# HexJacks.net
KiCad netlist of a schematic drawn in EAGLE
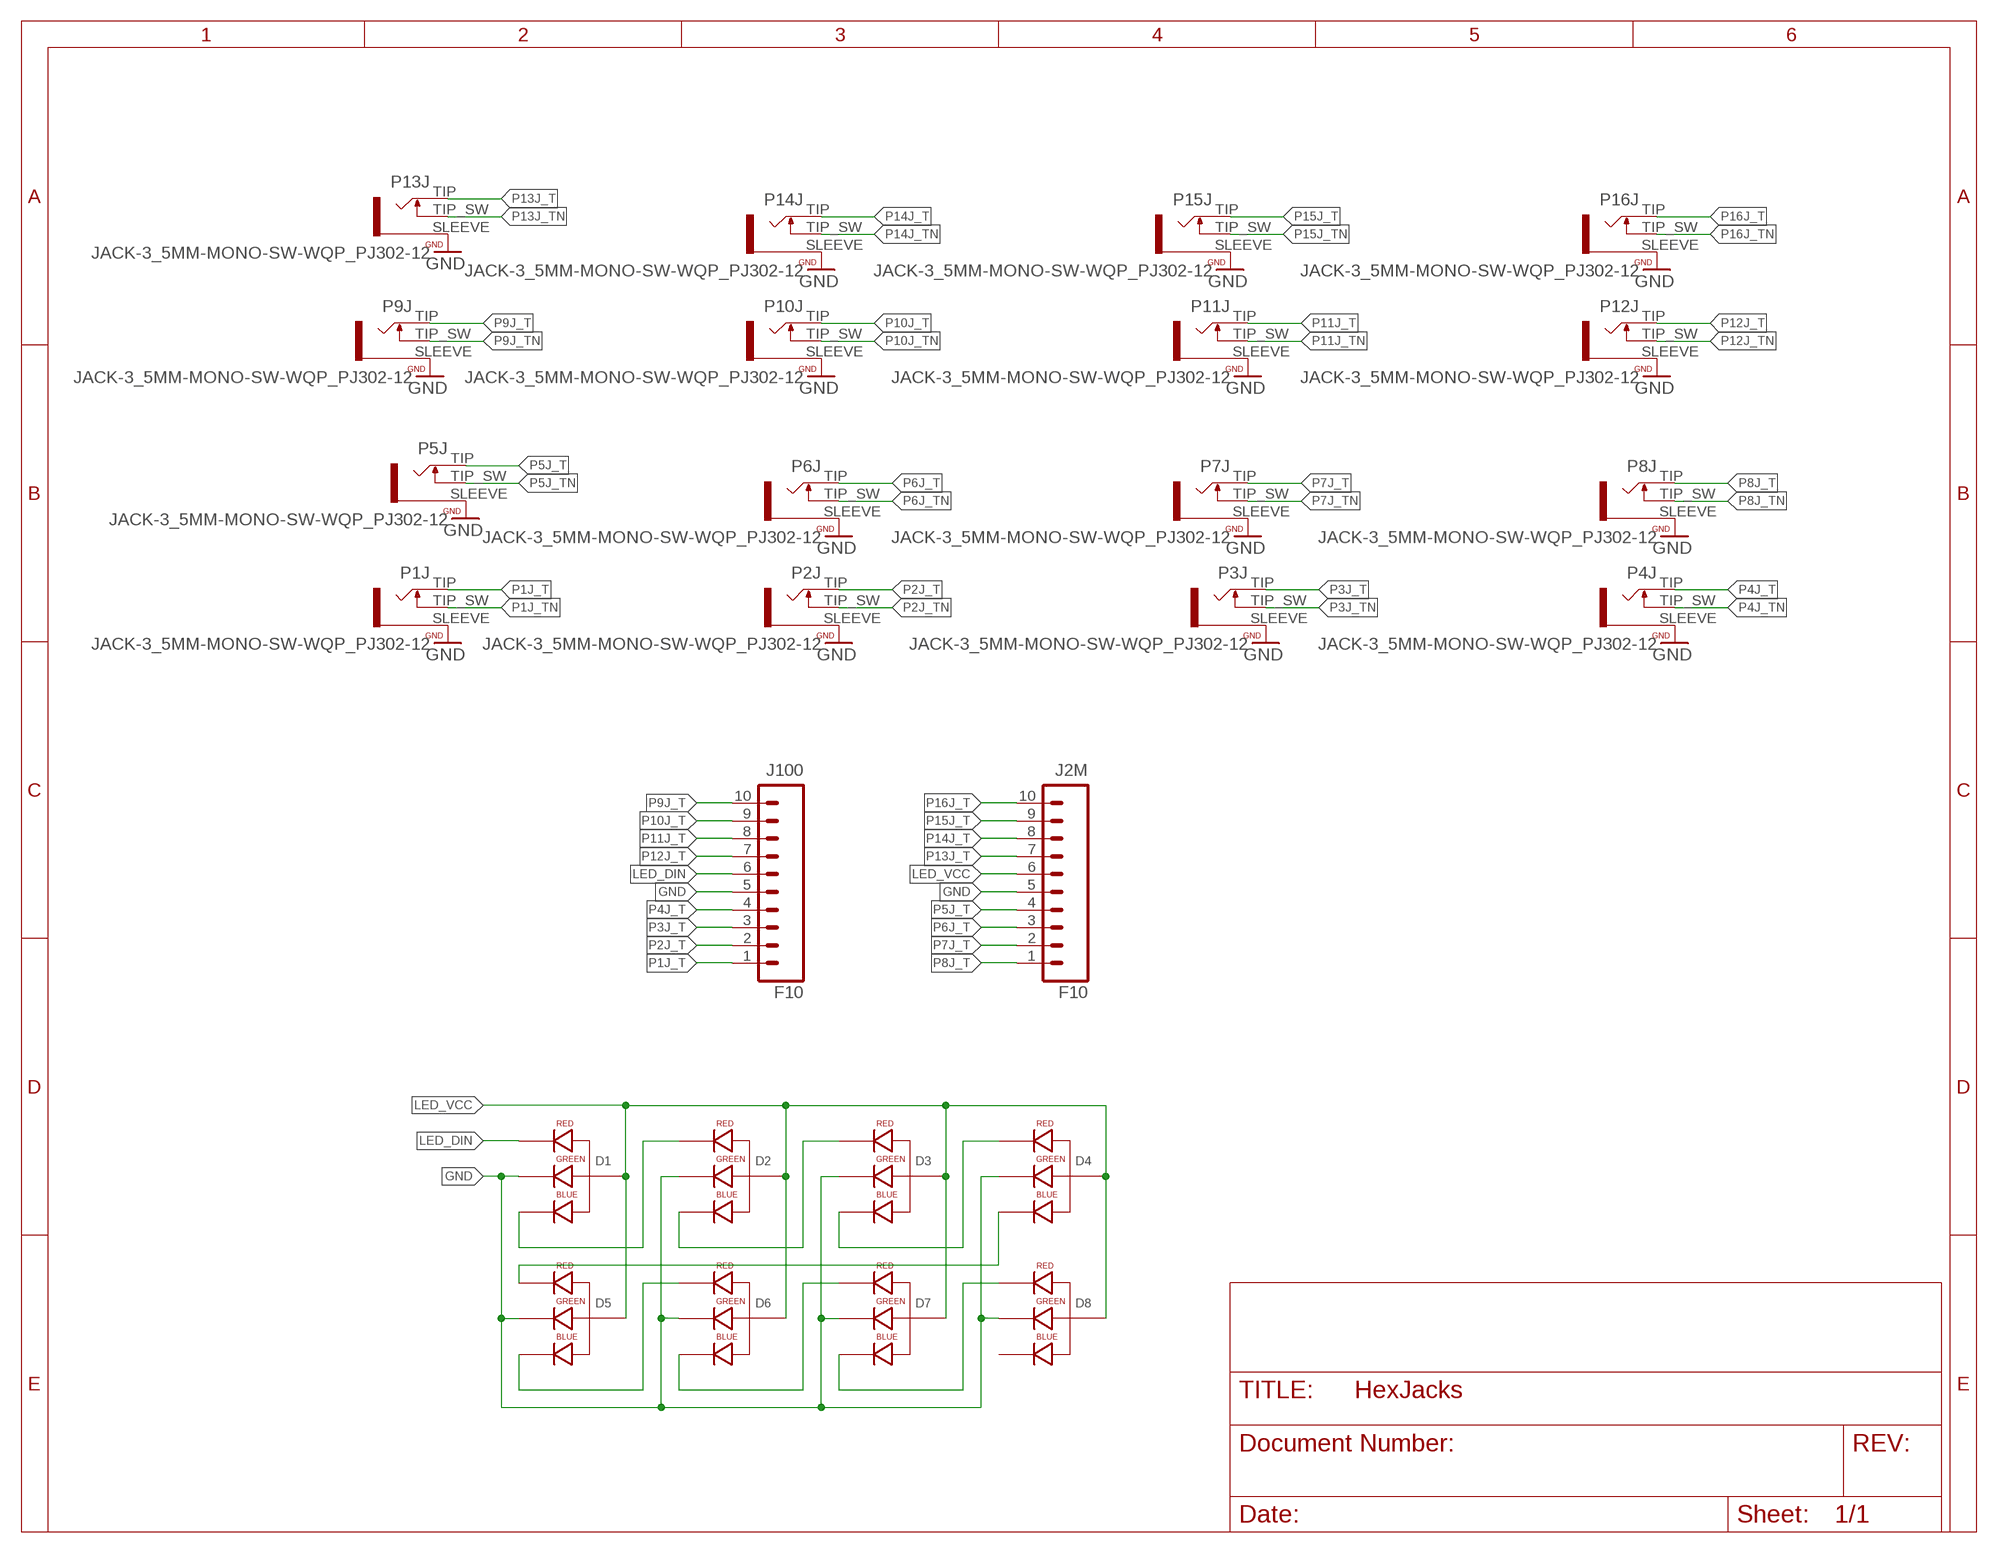
[diagram p0: schematic, sheet 1]

(export (version "E")
  (design (tool "Eeschema 10.0.6"))
  (components
    (comp (ref "D1")
      (value "LED-RGB-CA-THRUCLEAR")
      (footprint "eagle-import:LED-RGB-THRU")
      (libsource (lib "eagle-import") (part "LED-RGB-CA-THRUCLEAR"))
    )
    (comp (ref "D2")
      (value "LED-RGB-CA-THRUCLEAR")
      (footprint "eagle-import:LED-RGB-THRU")
      (libsource (lib "eagle-import") (part "LED-RGB-CA-THRUCLEAR"))
    )
    (comp (ref "D3")
      (value "LED-RGB-CA-THRUCLEAR")
      (footprint "eagle-import:LED-RGB-THRU")
      (libsource (lib "eagle-import") (part "LED-RGB-CA-THRUCLEAR"))
    )
    (comp (ref "D4")
      (value "LED-RGB-CA-THRUCLEAR")
      (footprint "eagle-import:LED-RGB-THRU")
      (libsource (lib "eagle-import") (part "LED-RGB-CA-THRUCLEAR"))
    )
    (comp (ref "D5")
      (value "LED-RGB-CA-THRUCLEAR")
      (footprint "eagle-import:LED-RGB-THRU")
      (libsource (lib "eagle-import") (part "LED-RGB-CA-THRUCLEAR"))
    )
    (comp (ref "D6")
      (value "LED-RGB-CA-THRUCLEAR")
      (footprint "eagle-import:LED-RGB-THRU")
      (libsource (lib "eagle-import") (part "LED-RGB-CA-THRUCLEAR"))
    )
    (comp (ref "D7")
      (value "LED-RGB-CA-THRUCLEAR")
      (footprint "eagle-import:LED-RGB-THRU")
      (libsource (lib "eagle-import") (part "LED-RGB-CA-THRUCLEAR"))
    )
    (comp (ref "D8")
      (value "LED-RGB-CA-THRUCLEAR")
      (footprint "eagle-import:LED-RGB-THRU")
      (libsource (lib "eagle-import") (part "LED-RGB-CA-THRUCLEAR"))
    )
    (comp (ref "J2M")
      (value "F10")
      (footprint "eagle-import:1X10_OCTO")
      (libsource (lib "eagle-import") (part "M10SILK_FEMALE_PTH"))
    )
    (comp (ref "J100")
      (value "F10")
      (footprint "eagle-import:1X10_OCTO")
      (libsource (lib "eagle-import") (part "M10SILK_FEMALE_PTH"))
    )
    (comp (ref "P1J")
      (value "JACK-3_5MM-MONO-SW-WQP_PJ302-12")
      (footprint "eagle-import:WQP_PJ301M-12")
      (libsource (lib "eagle-import") (part "JACK-3_5MM-MONO-SW-WQP_PJ302-12"))
    )
    (comp (ref "P2J")
      (value "JACK-3_5MM-MONO-SW-WQP_PJ302-12")
      (footprint "eagle-import:WQP_PJ301M-12")
      (libsource (lib "eagle-import") (part "JACK-3_5MM-MONO-SW-WQP_PJ302-12"))
    )
    (comp (ref "P3J")
      (value "JACK-3_5MM-MONO-SW-WQP_PJ302-12")
      (footprint "eagle-import:WQP_PJ301M-12")
      (libsource (lib "eagle-import") (part "JACK-3_5MM-MONO-SW-WQP_PJ302-12"))
    )
    (comp (ref "P4J")
      (value "JACK-3_5MM-MONO-SW-WQP_PJ302-12")
      (footprint "eagle-import:WQP_PJ301M-12")
      (libsource (lib "eagle-import") (part "JACK-3_5MM-MONO-SW-WQP_PJ302-12"))
    )
    (comp (ref "P5J")
      (value "JACK-3_5MM-MONO-SW-WQP_PJ302-12")
      (footprint "eagle-import:WQP_PJ301M-12")
      (libsource (lib "eagle-import") (part "JACK-3_5MM-MONO-SW-WQP_PJ302-12"))
    )
    (comp (ref "P6J")
      (value "JACK-3_5MM-MONO-SW-WQP_PJ302-12")
      (footprint "eagle-import:WQP_PJ301M-12")
      (libsource (lib "eagle-import") (part "JACK-3_5MM-MONO-SW-WQP_PJ302-12"))
    )
    (comp (ref "P7J")
      (value "JACK-3_5MM-MONO-SW-WQP_PJ302-12")
      (footprint "eagle-import:WQP_PJ301M-12")
      (libsource (lib "eagle-import") (part "JACK-3_5MM-MONO-SW-WQP_PJ302-12"))
    )
    (comp (ref "P8J")
      (value "JACK-3_5MM-MONO-SW-WQP_PJ302-12")
      (footprint "eagle-import:WQP_PJ301M-12")
      (libsource (lib "eagle-import") (part "JACK-3_5MM-MONO-SW-WQP_PJ302-12"))
    )
    (comp (ref "P9J")
      (value "JACK-3_5MM-MONO-SW-WQP_PJ302-12")
      (footprint "eagle-import:WQP_PJ301M-12")
      (libsource (lib "eagle-import") (part "JACK-3_5MM-MONO-SW-WQP_PJ302-12"))
    )
    (comp (ref "P10J")
      (value "JACK-3_5MM-MONO-SW-WQP_PJ302-12")
      (footprint "eagle-import:WQP_PJ301M-12")
      (libsource (lib "eagle-import") (part "JACK-3_5MM-MONO-SW-WQP_PJ302-12"))
    )
    (comp (ref "P11J")
      (value "JACK-3_5MM-MONO-SW-WQP_PJ302-12")
      (footprint "eagle-import:WQP_PJ301M-12")
      (libsource (lib "eagle-import") (part "JACK-3_5MM-MONO-SW-WQP_PJ302-12"))
    )
    (comp (ref "P12J")
      (value "JACK-3_5MM-MONO-SW-WQP_PJ302-12")
      (footprint "eagle-import:WQP_PJ301M-12")
      (libsource (lib "eagle-import") (part "JACK-3_5MM-MONO-SW-WQP_PJ302-12"))
    )
    (comp (ref "P13J")
      (value "JACK-3_5MM-MONO-SW-WQP_PJ302-12")
      (footprint "eagle-import:WQP_PJ301M-12")
      (libsource (lib "eagle-import") (part "JACK-3_5MM-MONO-SW-WQP_PJ302-12"))
    )
    (comp (ref "P14J")
      (value "JACK-3_5MM-MONO-SW-WQP_PJ302-12")
      (footprint "eagle-import:WQP_PJ301M-12")
      (libsource (lib "eagle-import") (part "JACK-3_5MM-MONO-SW-WQP_PJ302-12"))
    )
    (comp (ref "P15J")
      (value "JACK-3_5MM-MONO-SW-WQP_PJ302-12")
      (footprint "eagle-import:WQP_PJ301M-12")
      (libsource (lib "eagle-import") (part "JACK-3_5MM-MONO-SW-WQP_PJ302-12"))
    )
    (comp (ref "P16J")
      (value "JACK-3_5MM-MONO-SW-WQP_PJ302-12")
      (footprint "eagle-import:WQP_PJ301M-12")
      (libsource (lib "eagle-import") (part "JACK-3_5MM-MONO-SW-WQP_PJ302-12"))
    )
  )
  (nets
    (net (code "1") (name "GND") (class "Default")
      (node (ref "D1") (pin "3") (pinfunction "GREEN_CATHODE_3") (pintype "bidirectional"))
      (node (ref "D2") (pin "3") (pinfunction "GREEN_CATHODE_3") (pintype "bidirectional"))
      (node (ref "D3") (pin "3") (pinfunction "GREEN_CATHODE_3") (pintype "bidirectional"))
      (node (ref "D4") (pin "3") (pinfunction "GREEN_CATHODE_3") (pintype "bidirectional"))
      (node (ref "D5") (pin "3") (pinfunction "GREEN_CATHODE_3") (pintype "bidirectional"))
      (node (ref "D6") (pin "3") (pinfunction "GREEN_CATHODE_3") (pintype "bidirectional"))
      (node (ref "D7") (pin "3") (pinfunction "GREEN_CATHODE_3") (pintype "bidirectional"))
      (node (ref "D8") (pin "3") (pinfunction "GREEN_CATHODE_3") (pintype "bidirectional"))
      (node (ref "J100") (pin "5") (pinfunction "5_5") (pintype "passive"))
      (node (ref "J2M") (pin "5") (pinfunction "5_5") (pintype "passive"))
      (node (ref "P10J") (pin "SLEEVE") (pinfunction "SLEEVE_SLEEVE") (pintype "passive"))
      (node (ref "P11J") (pin "SLEEVE") (pinfunction "SLEEVE_SLEEVE") (pintype "passive"))
      (node (ref "P12J") (pin "SLEEVE") (pinfunction "SLEEVE_SLEEVE") (pintype "passive"))
      (node (ref "P13J") (pin "SLEEVE") (pinfunction "SLEEVE_SLEEVE") (pintype "passive"))
      (node (ref "P14J") (pin "SLEEVE") (pinfunction "SLEEVE_SLEEVE") (pintype "passive"))
      (node (ref "P15J") (pin "SLEEVE") (pinfunction "SLEEVE_SLEEVE") (pintype "passive"))
      (node (ref "P16J") (pin "SLEEVE") (pinfunction "SLEEVE_SLEEVE") (pintype "passive"))
      (node (ref "P1J") (pin "SLEEVE") (pinfunction "SLEEVE_SLEEVE") (pintype "passive"))
      (node (ref "P2J") (pin "SLEEVE") (pinfunction "SLEEVE_SLEEVE") (pintype "passive"))
      (node (ref "P3J") (pin "SLEEVE") (pinfunction "SLEEVE_SLEEVE") (pintype "passive"))
      (node (ref "P4J") (pin "SLEEVE") (pinfunction "SLEEVE_SLEEVE") (pintype "passive"))
      (node (ref "P5J") (pin "SLEEVE") (pinfunction "SLEEVE_SLEEVE") (pintype "passive"))
      (node (ref "P6J") (pin "SLEEVE") (pinfunction "SLEEVE_SLEEVE") (pintype "passive"))
      (node (ref "P7J") (pin "SLEEVE") (pinfunction "SLEEVE_SLEEVE") (pintype "passive"))
      (node (ref "P8J") (pin "SLEEVE") (pinfunction "SLEEVE_SLEEVE") (pintype "passive"))
      (node (ref "P9J") (pin "SLEEVE") (pinfunction "SLEEVE_SLEEVE") (pintype "passive"))
    )
    (net (code "2") (name "LED_DIN") (class "Default")
      (node (ref "D1") (pin "1") (pinfunction "RED_CATHODE_1") (pintype "bidirectional"))
      (node (ref "J100") (pin "6") (pinfunction "6_6") (pintype "passive"))
    )
    (net (code "3") (name "LED_VCC") (class "Default")
      (node (ref "D1") (pin "2") (pinfunction "ANODE_2") (pintype "bidirectional"))
      (node (ref "D2") (pin "2") (pinfunction "ANODE_2") (pintype "bidirectional"))
      (node (ref "D3") (pin "2") (pinfunction "ANODE_2") (pintype "bidirectional"))
      (node (ref "D4") (pin "2") (pinfunction "ANODE_2") (pintype "bidirectional"))
      (node (ref "D5") (pin "2") (pinfunction "ANODE_2") (pintype "bidirectional"))
      (node (ref "D6") (pin "2") (pinfunction "ANODE_2") (pintype "bidirectional"))
      (node (ref "D7") (pin "2") (pinfunction "ANODE_2") (pintype "bidirectional"))
      (node (ref "D8") (pin "2") (pinfunction "ANODE_2") (pintype "bidirectional"))
      (node (ref "J2M") (pin "6") (pinfunction "6_6") (pintype "passive"))
    )
    (net (code "4") (name "Net-(D1-BLUE_CATHODE)") (class "Default")
      (node (ref "D1") (pin "4") (pinfunction "BLUE_CATHODE_4") (pintype "bidirectional"))
      (node (ref "D2") (pin "1") (pinfunction "RED_CATHODE_1") (pintype "bidirectional"))
    )
    (net (code "5") (name "Net-(D2-BLUE_CATHODE)") (class "Default")
      (node (ref "D2") (pin "4") (pinfunction "BLUE_CATHODE_4") (pintype "bidirectional"))
      (node (ref "D3") (pin "1") (pinfunction "RED_CATHODE_1") (pintype "bidirectional"))
    )
    (net (code "6") (name "Net-(D3-BLUE_CATHODE)") (class "Default")
      (node (ref "D3") (pin "4") (pinfunction "BLUE_CATHODE_4") (pintype "bidirectional"))
      (node (ref "D4") (pin "1") (pinfunction "RED_CATHODE_1") (pintype "bidirectional"))
    )
    (net (code "7") (name "Net-(D4-BLUE_CATHODE)") (class "Default")
      (node (ref "D4") (pin "4") (pinfunction "BLUE_CATHODE_4") (pintype "bidirectional"))
      (node (ref "D5") (pin "1") (pinfunction "RED_CATHODE_1") (pintype "bidirectional"))
    )
    (net (code "8") (name "Net-(D5-BLUE_CATHODE)") (class "Default")
      (node (ref "D5") (pin "4") (pinfunction "BLUE_CATHODE_4") (pintype "bidirectional"))
      (node (ref "D6") (pin "1") (pinfunction "RED_CATHODE_1") (pintype "bidirectional"))
    )
    (net (code "9") (name "Net-(D6-BLUE_CATHODE)") (class "Default")
      (node (ref "D6") (pin "4") (pinfunction "BLUE_CATHODE_4") (pintype "bidirectional"))
      (node (ref "D7") (pin "1") (pinfunction "RED_CATHODE_1") (pintype "bidirectional"))
    )
    (net (code "10") (name "Net-(D7-BLUE_CATHODE)") (class "Default")
      (node (ref "D7") (pin "4") (pinfunction "BLUE_CATHODE_4") (pintype "bidirectional"))
      (node (ref "D8") (pin "1") (pinfunction "RED_CATHODE_1") (pintype "bidirectional"))
    )
    (net (code "11") (name "P1J_T") (class "Default")
      (node (ref "J100") (pin "1") (pinfunction "1_1") (pintype "passive"))
      (node (ref "P1J") (pin "TIP") (pinfunction "TIP_TIP") (pintype "passive"))
    )
    (net (code "12") (name "P1J_TN") (class "Default")
      (node (ref "P1J") (pin "TIP_SW") (pinfunction "TIP_SW_TIP_SW") (pintype "passive"))
    )
    (net (code "13") (name "P2J_T") (class "Default")
      (node (ref "J100") (pin "2") (pinfunction "2_2") (pintype "passive"))
      (node (ref "P2J") (pin "TIP") (pinfunction "TIP_TIP") (pintype "passive"))
    )
    (net (code "14") (name "P2J_TN") (class "Default")
      (node (ref "P2J") (pin "TIP_SW") (pinfunction "TIP_SW_TIP_SW") (pintype "passive"))
    )
    (net (code "15") (name "P3J_T") (class "Default")
      (node (ref "J100") (pin "3") (pinfunction "3_3") (pintype "passive"))
      (node (ref "P3J") (pin "TIP") (pinfunction "TIP_TIP") (pintype "passive"))
    )
    (net (code "16") (name "P3J_TN") (class "Default")
      (node (ref "P3J") (pin "TIP_SW") (pinfunction "TIP_SW_TIP_SW") (pintype "passive"))
    )
    (net (code "17") (name "P4J_T") (class "Default")
      (node (ref "J100") (pin "4") (pinfunction "4_4") (pintype "passive"))
      (node (ref "P4J") (pin "TIP") (pinfunction "TIP_TIP") (pintype "passive"))
    )
    (net (code "18") (name "P4J_TN") (class "Default")
      (node (ref "P4J") (pin "TIP_SW") (pinfunction "TIP_SW_TIP_SW") (pintype "passive"))
    )
    (net (code "19") (name "P5J_T") (class "Default")
      (node (ref "J2M") (pin "4") (pinfunction "4_4") (pintype "passive"))
      (node (ref "P5J") (pin "TIP") (pinfunction "TIP_TIP") (pintype "passive"))
    )
    (net (code "20") (name "P5J_TN") (class "Default")
      (node (ref "P5J") (pin "TIP_SW") (pinfunction "TIP_SW_TIP_SW") (pintype "passive"))
    )
    (net (code "21") (name "P6J_T") (class "Default")
      (node (ref "J2M") (pin "3") (pinfunction "3_3") (pintype "passive"))
      (node (ref "P6J") (pin "TIP") (pinfunction "TIP_TIP") (pintype "passive"))
    )
    (net (code "22") (name "P6J_TN") (class "Default")
      (node (ref "P6J") (pin "TIP_SW") (pinfunction "TIP_SW_TIP_SW") (pintype "passive"))
    )
    (net (code "23") (name "P7J_T") (class "Default")
      (node (ref "J2M") (pin "2") (pinfunction "2_2") (pintype "passive"))
      (node (ref "P7J") (pin "TIP") (pinfunction "TIP_TIP") (pintype "passive"))
    )
    (net (code "24") (name "P7J_TN") (class "Default")
      (node (ref "P7J") (pin "TIP_SW") (pinfunction "TIP_SW_TIP_SW") (pintype "passive"))
    )
    (net (code "25") (name "P8J_T") (class "Default")
      (node (ref "J2M") (pin "1") (pinfunction "1_1") (pintype "passive"))
      (node (ref "P8J") (pin "TIP") (pinfunction "TIP_TIP") (pintype "passive"))
    )
    (net (code "26") (name "P8J_TN") (class "Default")
      (node (ref "P8J") (pin "TIP_SW") (pinfunction "TIP_SW_TIP_SW") (pintype "passive"))
    )
    (net (code "27") (name "P9J_T") (class "Default")
      (node (ref "J100") (pin "10") (pinfunction "10_10") (pintype "passive"))
      (node (ref "P9J") (pin "TIP") (pinfunction "TIP_TIP") (pintype "passive"))
    )
    (net (code "28") (name "P9J_TN") (class "Default")
      (node (ref "P9J") (pin "TIP_SW") (pinfunction "TIP_SW_TIP_SW") (pintype "passive"))
    )
    (net (code "29") (name "P10J_T") (class "Default")
      (node (ref "J100") (pin "9") (pinfunction "9_9") (pintype "passive"))
      (node (ref "P10J") (pin "TIP") (pinfunction "TIP_TIP") (pintype "passive"))
    )
    (net (code "30") (name "P10J_TN") (class "Default")
      (node (ref "P10J") (pin "TIP_SW") (pinfunction "TIP_SW_TIP_SW") (pintype "passive"))
    )
    (net (code "31") (name "P11J_T") (class "Default")
      (node (ref "J100") (pin "8") (pinfunction "8_8") (pintype "passive"))
      (node (ref "P11J") (pin "TIP") (pinfunction "TIP_TIP") (pintype "passive"))
    )
    (net (code "32") (name "P11J_TN") (class "Default")
      (node (ref "P11J") (pin "TIP_SW") (pinfunction "TIP_SW_TIP_SW") (pintype "passive"))
    )
    (net (code "33") (name "P12J_T") (class "Default")
      (node (ref "J100") (pin "7") (pinfunction "7_7") (pintype "passive"))
      (node (ref "P12J") (pin "TIP") (pinfunction "TIP_TIP") (pintype "passive"))
    )
    (net (code "34") (name "P12J_TN") (class "Default")
      (node (ref "P12J") (pin "TIP_SW") (pinfunction "TIP_SW_TIP_SW") (pintype "passive"))
    )
    (net (code "35") (name "P13J_T") (class "Default")
      (node (ref "J2M") (pin "7") (pinfunction "7_7") (pintype "passive"))
      (node (ref "P13J") (pin "TIP") (pinfunction "TIP_TIP") (pintype "passive"))
    )
    (net (code "36") (name "P13J_TN") (class "Default")
      (node (ref "P13J") (pin "TIP_SW") (pinfunction "TIP_SW_TIP_SW") (pintype "passive"))
    )
    (net (code "37") (name "P14J_T") (class "Default")
      (node (ref "J2M") (pin "8") (pinfunction "8_8") (pintype "passive"))
      (node (ref "P14J") (pin "TIP") (pinfunction "TIP_TIP") (pintype "passive"))
    )
    (net (code "38") (name "P14J_TN") (class "Default")
      (node (ref "P14J") (pin "TIP_SW") (pinfunction "TIP_SW_TIP_SW") (pintype "passive"))
    )
    (net (code "39") (name "P15J_T") (class "Default")
      (node (ref "J2M") (pin "9") (pinfunction "9_9") (pintype "passive"))
      (node (ref "P15J") (pin "TIP") (pinfunction "TIP_TIP") (pintype "passive"))
    )
    (net (code "40") (name "P15J_TN") (class "Default")
      (node (ref "P15J") (pin "TIP_SW") (pinfunction "TIP_SW_TIP_SW") (pintype "passive"))
    )
    (net (code "41") (name "P16J_T") (class "Default")
      (node (ref "J2M") (pin "10") (pinfunction "10_10") (pintype "passive"))
      (node (ref "P16J") (pin "TIP") (pinfunction "TIP_TIP") (pintype "passive"))
    )
    (net (code "42") (name "P16J_TN") (class "Default")
      (node (ref "P16J") (pin "TIP_SW") (pinfunction "TIP_SW_TIP_SW") (pintype "passive"))
    )
    (net (code "43") (name "unconnected-(D8-BLUE_CATHODE-Pad4)") (class "Default")
      (node (ref "D8") (pin "4") (pinfunction "BLUE_CATHODE_4") (pintype "bidirectional"))
    )
  )
)
